# Simple_Heart_v2_-_grounded.net
KiCad netlist of a schematic drawn in EAGLE
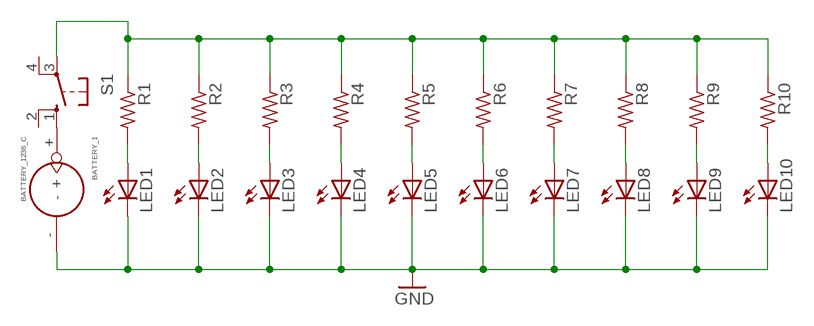
[diagram p0: schematic, sheet 1]

(export (version "E")
  (design (tool "Eeschema 10.0.6"))
  (components
    (comp (ref "BATTERY_1")
      (value "BATTERY_1236_C")
      (footprint "eagle-import:BATTERY_1236_C")
      (libsource (lib "eagle-import") (part "BATTERY_1236_C"))
    )
    (comp (ref "LED1")
      (value "LED5MM")
      (footprint "eagle-import:LED5MM")
      (libsource (lib "eagle-import") (part "LED5MM"))
    )
    (comp (ref "LED2")
      (value "LED5MM")
      (footprint "eagle-import:LED5MM")
      (libsource (lib "eagle-import") (part "LED5MM"))
    )
    (comp (ref "LED3")
      (value "LED5MM")
      (footprint "eagle-import:LED5MM")
      (libsource (lib "eagle-import") (part "LED5MM"))
    )
    (comp (ref "LED4")
      (value "LED5MM")
      (footprint "eagle-import:LED5MM")
      (libsource (lib "eagle-import") (part "LED5MM"))
    )
    (comp (ref "LED5")
      (value "LED5MM")
      (footprint "eagle-import:LED5MM")
      (libsource (lib "eagle-import") (part "LED5MM"))
    )
    (comp (ref "LED6")
      (value "LED5MM")
      (footprint "eagle-import:LED5MM")
      (libsource (lib "eagle-import") (part "LED5MM"))
    )
    (comp (ref "LED7")
      (value "LED5MM")
      (footprint "eagle-import:LED5MM")
      (libsource (lib "eagle-import") (part "LED5MM"))
    )
    (comp (ref "LED8")
      (value "LED5MM")
      (footprint "eagle-import:LED5MM")
      (libsource (lib "eagle-import") (part "LED5MM"))
    )
    (comp (ref "LED9")
      (value "LED5MM")
      (footprint "eagle-import:LED5MM")
      (libsource (lib "eagle-import") (part "LED5MM"))
    )
    (comp (ref "LED10")
      (value "LED5MM")
      (footprint "eagle-import:LED5MM")
      (libsource (lib "eagle-import") (part "LED5MM"))
    )
    (comp (ref "R1")
      (value "R-US_0204/7")
      (footprint "eagle-import:0204_7")
      (libsource (lib "eagle-import") (part "R-US_0204/7"))
    )
    (comp (ref "R2")
      (value "R-US_0204/7")
      (footprint "eagle-import:0204_7")
      (libsource (lib "eagle-import") (part "R-US_0204/7"))
    )
    (comp (ref "R3")
      (value "R-US_0204/7")
      (footprint "eagle-import:0204_7")
      (libsource (lib "eagle-import") (part "R-US_0204/7"))
    )
    (comp (ref "R4")
      (value "R-US_0204/7")
      (footprint "eagle-import:0204_7")
      (libsource (lib "eagle-import") (part "R-US_0204/7"))
    )
    (comp (ref "R5")
      (value "R-US_0204/7")
      (footprint "eagle-import:0204_7")
      (libsource (lib "eagle-import") (part "R-US_0204/7"))
    )
    (comp (ref "R6")
      (value "R-US_0204/7")
      (footprint "eagle-import:0204_7")
      (libsource (lib "eagle-import") (part "R-US_0204/7"))
    )
    (comp (ref "R7")
      (value "R-US_0204/7")
      (footprint "eagle-import:0204_7")
      (libsource (lib "eagle-import") (part "R-US_0204/7"))
    )
    (comp (ref "R8")
      (value "R-US_0204/7")
      (footprint "eagle-import:0204_7")
      (libsource (lib "eagle-import") (part "R-US_0204/7"))
    )
    (comp (ref "R9")
      (value "R-US_0204/7")
      (footprint "eagle-import:0204_7")
      (libsource (lib "eagle-import") (part "R-US_0204/7"))
    )
    (comp (ref "R10")
      (value "R-US_0204/7")
      (footprint "eagle-import:0204_7")
      (libsource (lib "eagle-import") (part "R-US_0204/7"))
    )
    (comp (ref "S1")
      (value "10-XX")
      (footprint "eagle-import:B3F-10XX")
      (fields (field (name "MPN") "B3F-1000"))
      (libsource (lib "eagle-import") (part "10-XX"))
    )
  )
  (nets
    (net (code "1") (name "GND") (class "Default")
      (node (ref "BATTERY_1") (pin "-") (pinfunction "-_-") (pintype "bidirectional"))
      (node (ref "LED1") (pin "K") (pinfunction "C_K") (pintype "passive"))
      (node (ref "LED10") (pin "K") (pinfunction "C_K") (pintype "passive"))
      (node (ref "LED2") (pin "K") (pinfunction "C_K") (pintype "passive"))
      (node (ref "LED3") (pin "K") (pinfunction "C_K") (pintype "passive"))
      (node (ref "LED4") (pin "K") (pinfunction "C_K") (pintype "passive"))
      (node (ref "LED5") (pin "K") (pinfunction "C_K") (pintype "passive"))
      (node (ref "LED6") (pin "K") (pinfunction "C_K") (pintype "passive"))
      (node (ref "LED7") (pin "K") (pinfunction "C_K") (pintype "passive"))
      (node (ref "LED8") (pin "K") (pinfunction "C_K") (pintype "passive"))
      (node (ref "LED9") (pin "K") (pinfunction "C_K") (pintype "passive"))
    )
    (net (code "2") (name "Net-(LED1-PadA)") (class "Default")
      (node (ref "LED1") (pin "A") (pinfunction "A_A") (pintype "passive"))
      (node (ref "R1") (pin "2") (pinfunction "2_2") (pintype "passive"))
    )
    (net (code "3") (name "Net-(LED2-PadA)") (class "Default")
      (node (ref "LED2") (pin "A") (pinfunction "A_A") (pintype "passive"))
      (node (ref "R2") (pin "2") (pinfunction "2_2") (pintype "passive"))
    )
    (net (code "4") (name "Net-(LED3-PadA)") (class "Default")
      (node (ref "LED3") (pin "A") (pinfunction "A_A") (pintype "passive"))
      (node (ref "R3") (pin "2") (pinfunction "2_2") (pintype "passive"))
    )
    (net (code "5") (name "Net-(LED4-PadA)") (class "Default")
      (node (ref "LED4") (pin "A") (pinfunction "A_A") (pintype "passive"))
      (node (ref "R4") (pin "2") (pinfunction "2_2") (pintype "passive"))
    )
    (net (code "6") (name "Net-(LED5-PadA)") (class "Default")
      (node (ref "LED5") (pin "A") (pinfunction "A_A") (pintype "passive"))
      (node (ref "R5") (pin "2") (pinfunction "2_2") (pintype "passive"))
    )
    (net (code "7") (name "Net-(LED6-PadA)") (class "Default")
      (node (ref "LED6") (pin "A") (pinfunction "A_A") (pintype "passive"))
      (node (ref "R6") (pin "2") (pinfunction "2_2") (pintype "passive"))
    )
    (net (code "8") (name "Net-(LED7-PadA)") (class "Default")
      (node (ref "LED7") (pin "A") (pinfunction "A_A") (pintype "passive"))
      (node (ref "R7") (pin "2") (pinfunction "2_2") (pintype "passive"))
    )
    (net (code "9") (name "Net-(LED8-PadA)") (class "Default")
      (node (ref "LED8") (pin "A") (pinfunction "A_A") (pintype "passive"))
      (node (ref "R8") (pin "2") (pinfunction "2_2") (pintype "passive"))
    )
    (net (code "10") (name "Net-(LED9-PadA)") (class "Default")
      (node (ref "LED9") (pin "A") (pinfunction "A_A") (pintype "passive"))
      (node (ref "R9") (pin "2") (pinfunction "2_2") (pintype "passive"))
    )
    (net (code "11") (name "Net-(LED10-PadA)") (class "Default")
      (node (ref "LED10") (pin "A") (pinfunction "A_A") (pintype "passive"))
      (node (ref "R10") (pin "2") (pinfunction "2_2") (pintype "passive"))
    )
    (net (code "12") (name "Net-(S1-P)") (class "Default")
      (node (ref "R1") (pin "1") (pinfunction "1_1") (pintype "passive"))
      (node (ref "R10") (pin "1") (pinfunction "1_1") (pintype "passive"))
      (node (ref "R2") (pin "1") (pinfunction "1_1") (pintype "passive"))
      (node (ref "R3") (pin "1") (pinfunction "1_1") (pintype "passive"))
      (node (ref "R4") (pin "1") (pinfunction "1_1") (pintype "passive"))
      (node (ref "R5") (pin "1") (pinfunction "1_1") (pintype "passive"))
      (node (ref "R6") (pin "1") (pinfunction "1_1") (pintype "passive"))
      (node (ref "R7") (pin "1") (pinfunction "1_1") (pintype "passive"))
      (node (ref "R8") (pin "1") (pinfunction "1_1") (pintype "passive"))
      (node (ref "R9") (pin "1") (pinfunction "1_1") (pintype "passive"))
      (node (ref "S1") (pin "3") (pinfunction "P_3") (pintype "passive"))
    )
    (net (code "13") (name "Net-(S1-S)") (class "Default")
      (node (ref "BATTERY_1") (pin "+") (pinfunction "+_+") (pintype "bidirectional"))
      (node (ref "S1") (pin "1") (pinfunction "S_1") (pintype "passive"))
    )
    (net (code "14") (name "unconnected-(S1-P1-Pad4)") (class "Default")
      (node (ref "S1") (pin "4") (pinfunction "P1_4") (pintype "passive"))
    )
    (net (code "15") (name "unconnected-(S1-S1-Pad2)") (class "Default")
      (node (ref "S1") (pin "2") (pinfunction "S1_2") (pintype "passive"))
    )
  )
)
